# Logger_Schematic.net
KiCad netlist of a schematic drawn in Altium Designer
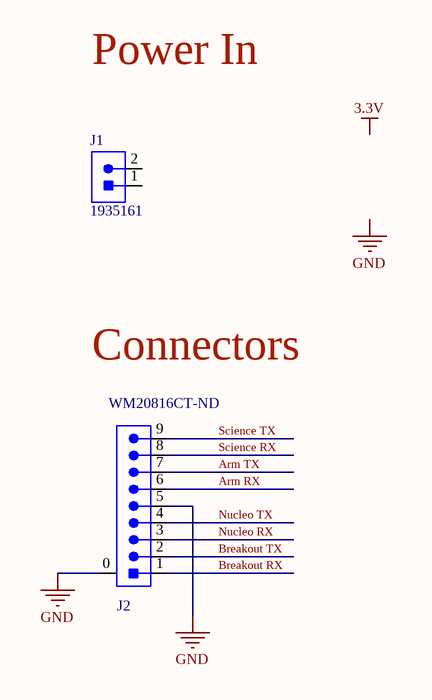
[diagram p0: Logger Schematic.SchDoc]

(export (version "E")
  (design (tool "Eeschema 10.0.6"))
  (components
    (comp (ref "J1")
      (value "1935161")
      (footprint "1935161")
      (description "TERM BLK 2POS SIDE ENTRY 5MM")
      (fields (field (name "VOLTAGE") "300V") (field (name "MANUFACTURER PART NUMBER 1") "1935161"))
      (libsource (lib "UWRT_Schematic_Library_2020") (part "CON_2M_TERM"))
    )
    (comp (ref "J2")
      (value "CON_9M_SM_RA")
      (footprint "Molex-5025850970")
      (description "CONN RCPT 9POS CLIK-MATE 0.059 TIN SMD R/A")
      (fields
        (field (name "MANUFACTURER") "Molex")
        (field (name "MANUFACTURER PART NUMBER") "5025850970")
        (field (name "SUPPLIER PART NUMBER 1") "WM20816CT-ND")
      )
      (libsource (lib "UWRT_Schematic_Library_2020") (part "CON_9M_SM_RA"))
    )
  )
  (nets
    (net (code "1") (name "/Arm RX") (class "Default")
      (node (ref "J2") (pin "6") (pinfunction "6_6") (pintype "passive"))
    )
    (net (code "2") (name "/Arm TX") (class "Default")
      (node (ref "J2") (pin "7") (pinfunction "6_7") (pintype "passive"))
    )
    (net (code "3") (name "/Breakout RX") (class "Default")
      (node (ref "J2") (pin "1") (pinfunction "1_1") (pintype "passive"))
    )
    (net (code "4") (name "/Breakout TX") (class "Default")
      (node (ref "J2") (pin "2") (pinfunction "2_2") (pintype "passive"))
    )
    (net (code "5") (name "/Nucleo RX") (class "Default")
      (node (ref "J2") (pin "3") (pinfunction "3_3") (pintype "passive"))
    )
    (net (code "6") (name "/Nucleo TX") (class "Default")
      (node (ref "J2") (pin "4") (pinfunction "4_4") (pintype "passive"))
    )
    (net (code "7") (name "/Science RX") (class "Default")
      (node (ref "J2") (pin "8") (pinfunction "6_8") (pintype "passive"))
    )
    (net (code "8") (name "/Science TX") (class "Default")
      (node (ref "J2") (pin "9") (pinfunction "9_9") (pintype "passive"))
    )
    (net (code "10") (name "GND") (class "Default")
      (node (ref "J2") (pin "0") (pinfunction "0_0") (pintype "passive"))
      (node (ref "J2") (pin "5") (pinfunction "5_5") (pintype "passive"))
    )
    (net (code "11") (name "unconnected-(J1-Pad1)") (class "Default")
      (node (ref "J1") (pin "1") (pinfunction "1_1") (pintype "passive"))
    )
    (net (code "12") (name "unconnected-(J1-Pad2)") (class "Default")
      (node (ref "J1") (pin "2") (pinfunction "2_2") (pintype "passive"))
    )
  )
)
